# interface-2-cart.net
KiCad netlist of a schematic drawn in EAGLE
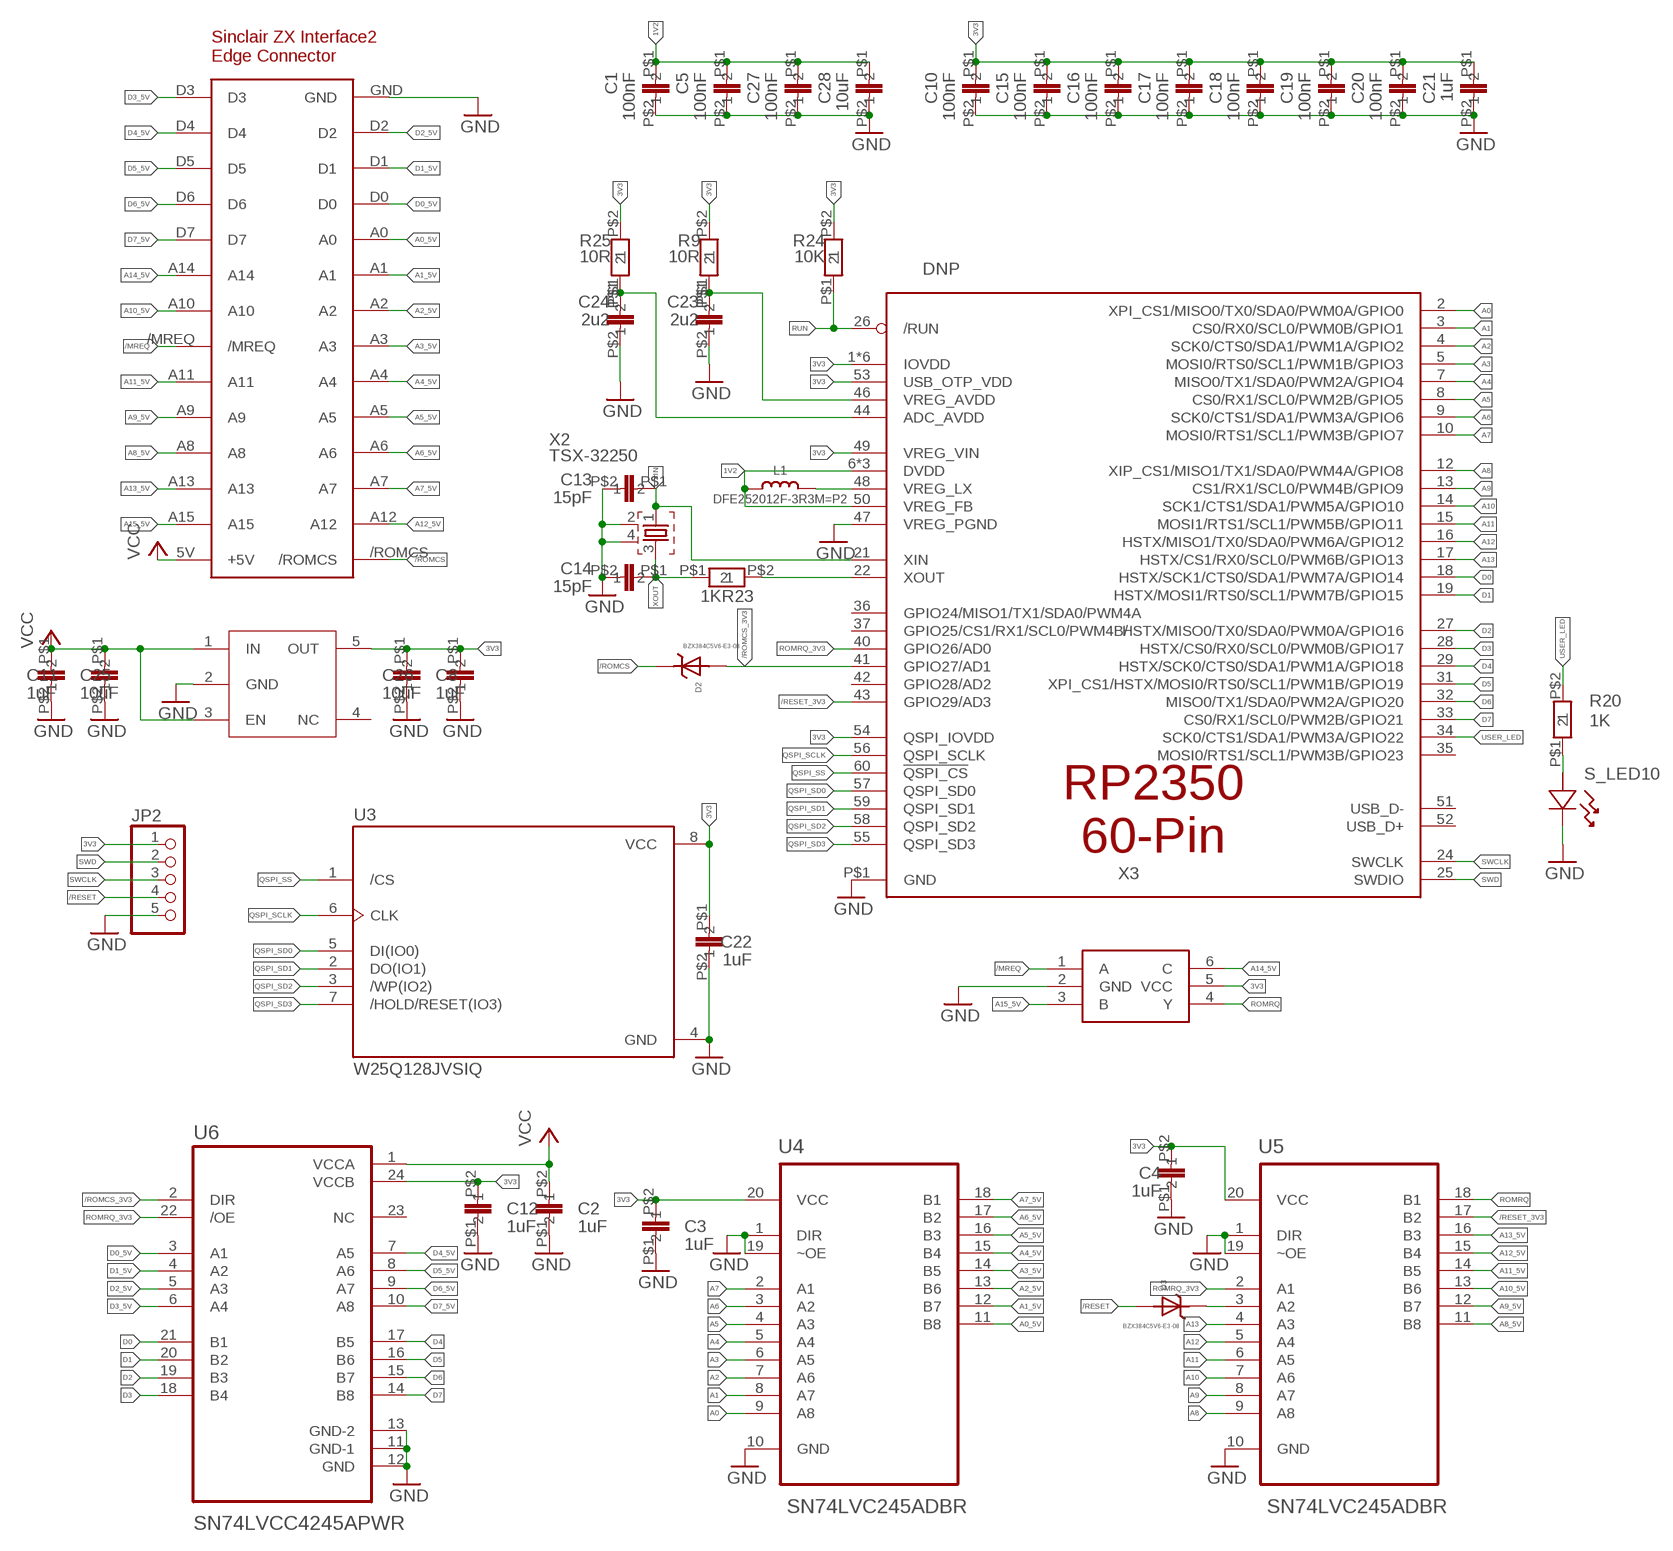
[diagram p0: schematic, sheet 1]

(export (version "E")
  (design (tool "Eeschema 10.0.6"))
  (components
    (comp (ref "3V3_REG2")
      (value "3V3")
      (footprint "eagle-import:NCP718BSN330T1G")
      (libsource (lib "eagle-import") (part "NCP718BSN330T1G"))
    )
    (comp (ref "C1")
      (value "100nF")
      (footprint "eagle-import:C0402")
      (libsource (lib "eagle-import") (part "CAP-0402"))
    )
    (comp (ref "C2")
      (value "1uF")
      (footprint "eagle-import:C0402")
      (libsource (lib "eagle-import") (part "CAP-0402"))
    )
    (comp (ref "C3")
      (value "1uF")
      (footprint "eagle-import:C0402")
      (libsource (lib "eagle-import") (part "CAP-0402"))
    )
    (comp (ref "C4")
      (value "1uF")
      (footprint "eagle-import:C0402")
      (libsource (lib "eagle-import") (part "CAP-0402"))
    )
    (comp (ref "C5")
      (value "100nF")
      (footprint "eagle-import:C0402")
      (libsource (lib "eagle-import") (part "CAP-0402"))
    )
    (comp (ref "C8")
      (value "1uF")
      (footprint "eagle-import:C0402")
      (libsource (lib "eagle-import") (part "CAP-0402"))
    )
    (comp (ref "C10")
      (value "100nF")
      (footprint "eagle-import:C0402")
      (libsource (lib "eagle-import") (part "CAP-0402"))
    )
    (comp (ref "C11")
      (value "1uF")
      (footprint "eagle-import:C0402")
      (libsource (lib "eagle-import") (part "CAP-0402"))
    )
    (comp (ref "C12")
      (value "1uF")
      (footprint "eagle-import:C0402")
      (libsource (lib "eagle-import") (part "CAP-0402"))
    )
    (comp (ref "C13")
      (value "15pF")
      (footprint "eagle-import:C0402")
      (libsource (lib "eagle-import") (part "CAP-0402"))
    )
    (comp (ref "C14")
      (value "15pF")
      (footprint "eagle-import:C0402")
      (libsource (lib "eagle-import") (part "CAP-0402"))
    )
    (comp (ref "C15")
      (value "100nF")
      (footprint "eagle-import:C0402")
      (libsource (lib "eagle-import") (part "CAP-0402"))
    )
    (comp (ref "C16")
      (value "100nF")
      (footprint "eagle-import:C0402")
      (libsource (lib "eagle-import") (part "CAP-0402"))
    )
    (comp (ref "C17")
      (value "100nF")
      (footprint "eagle-import:C0402")
      (libsource (lib "eagle-import") (part "CAP-0402"))
    )
    (comp (ref "C18")
      (value "100nF")
      (footprint "eagle-import:C0402")
      (libsource (lib "eagle-import") (part "CAP-0402"))
    )
    (comp (ref "C19")
      (value "100nF")
      (footprint "eagle-import:C0402")
      (libsource (lib "eagle-import") (part "CAP-0402"))
    )
    (comp (ref "C20")
      (value "100nF")
      (footprint "eagle-import:C0402")
      (libsource (lib "eagle-import") (part "CAP-0402"))
    )
    (comp (ref "C21")
      (value "1uF")
      (footprint "eagle-import:C0402")
      (libsource (lib "eagle-import") (part "CAP-0402"))
    )
    (comp (ref "C22")
      (value "1uF")
      (footprint "eagle-import:C0402")
      (libsource (lib "eagle-import") (part "CAP-0402"))
    )
    (comp (ref "C23")
      (value "2u2")
      (footprint "eagle-import:C0402")
      (libsource (lib "eagle-import") (part "CAP-0402"))
    )
    (comp (ref "C24")
      (value "2u2")
      (footprint "eagle-import:C0402")
      (libsource (lib "eagle-import") (part "CAP-0402"))
    )
    (comp (ref "C25")
      (value "10uF")
      (footprint "eagle-import:C0402")
      (libsource (lib "eagle-import") (part "CAP-0402"))
    )
    (comp (ref "C26")
      (value "10uF")
      (footprint "eagle-import:C0402")
      (libsource (lib "eagle-import") (part "CAP-0402"))
    )
    (comp (ref "C27")
      (value "100nF")
      (footprint "eagle-import:C0402")
      (libsource (lib "eagle-import") (part "CAP-0402"))
    )
    (comp (ref "C28")
      (value "10uF")
      (footprint "eagle-import:C0402")
      (libsource (lib "eagle-import") (part "CAP-0402"))
    )
    (comp (ref "D2")
      (value "BZX384C5V6-E3-08")
      (footprint "eagle-import:SOD-323")
      (fields (field (name "MF") "Vishay Semiconductors"))
      (libsource (lib "eagle-import") (part "BZX384C5V6-E3-08"))
    )
    (comp (ref "D3")
      (value "BZX384C5V6-E3-08")
      (footprint "eagle-import:SOD-323")
      (fields (field (name "MF") "Vishay Semiconductors"))
      (libsource (lib "eagle-import") (part "BZX384C5V6-E3-08"))
    )
    (comp (ref "JP2")
      (value "PINHD-1X5")
      (footprint "eagle-import:1X05")
      (libsource (lib "eagle-import") (part "PINHD-1X5"))
    )
    (comp (ref "L1")
      (value "DFE252012F-3R3M=P2")
      (footprint "eagle-import:INDUCTOR_1007")
      (libsource (lib "eagle-import") (part "INDUCTOR"))
    )
    (comp (ref "R9")
      (value "10R")
      (footprint "eagle-import:0402")
      (libsource (lib "eagle-import") (part "RES-0402"))
    )
    (comp (ref "R20")
      (value "1K")
      (footprint "eagle-import:0402")
      (libsource (lib "eagle-import") (part "RES-0402"))
    )
    (comp (ref "R23")
      (value "1K")
      (footprint "eagle-import:0402")
      (libsource (lib "eagle-import") (part "RES-0402"))
    )
    (comp (ref "R24")
      (value "10K")
      (footprint "eagle-import:0402")
      (libsource (lib "eagle-import") (part "RES-0402"))
    )
    (comp (ref "R25")
      (value "10R")
      (footprint "eagle-import:0402")
      (libsource (lib "eagle-import") (part "RES-0402"))
    )
    (comp (ref "S_LED10")
      (value "20mA")
      (footprint "eagle-import:LED_VLMW15_VIS")
      (fields
        (field (name "MANUFACTURER_PART_NUMBER") "VLMW1500-GS08")
        (field (name "COPYRIGHT") "Copyright (C) 2022 Ultra Librarian. All rights reserved.")
      )
      (libsource (lib "eagle-import") (part "VLMW1500-GS08"))
    )
    (comp (ref "U$1")
      (value "ZX_I2_ROM_EDGE_CONNECTOR")
      (footprint "eagle-import:ZX_I2_ROM_EDGE_CONNECTOR_V2")
      (libsource (lib "eagle-import") (part "ZX_I2_ROM_EDGE_CONNECTOR"))
    )
    (comp (ref "U$2")
      (value "74LVC1G332GW,125")
      (footprint "eagle-import:SOP65P210X110-6N")
      (libsource (lib "eagle-import") (part "74LVC1G332GW,125"))
    )
    (comp (ref "U3")
      (value "W25Q128JVSIQ")
      (footprint "eagle-import:SOIC127P790X216-8N")
      (fields (field (name "MF") "Winbond Electronics"))
      (libsource (lib "eagle-import") (part "W25Q128JVSIQ"))
    )
    (comp (ref "U4")
      (value "SN74LVC245ADBR")
      (footprint "eagle-import:SOP65P780X200-20N")
      (fields (field (name "MF") "Texas Instruments"))
      (libsource (lib "eagle-import") (part "SN74LVC245ADBR"))
    )
    (comp (ref "U5")
      (value "SN74LVC245ADBR")
      (footprint "eagle-import:SOP65P780X200-20N")
      (fields (field (name "MF") "Texas Instruments"))
      (libsource (lib "eagle-import") (part "SN74LVC245ADBR"))
    )
    (comp (ref "U6")
      (value "SN74LVCC4245APWR")
      (footprint "eagle-import:SOP65P640X120-24N")
      (fields (field (name "MF") "Texas Instruments"))
      (libsource (lib "eagle-import") (part "SN74LVCC4245APWR"))
    )
    (comp (ref "X2")
      (value "TSX-32250")
      (footprint "eagle-import:TSX-3225")
      (fields (field (name "MF") "EPSON") (field (name "MP") "TSX-3225"))
      (libsource (lib "eagle-import") (part "TSX-32250"))
    )
    (comp (ref "X3")
      (value "DNP")
      (footprint "eagle-import:QFN60_7MM_REDUCEDEPAD")
      (libsource (lib "eagle-import") (part "RP2350_QFN60"))
    )
  )
  (nets
    (net (code "1") (name "1V2") (class "Default")
      (node (ref "C1") (pin "P$1") (pinfunction "1_P$1") (pintype "passive"))
      (node (ref "C27") (pin "P$1") (pinfunction "1_P$1") (pintype "passive"))
      (node (ref "C28") (pin "P$1") (pinfunction "1_P$1") (pintype "passive"))
      (node (ref "C5") (pin "P$1") (pinfunction "1_P$1") (pintype "passive"))
      (node (ref "L1") (pin "P$1") (pinfunction "1_P$1") (pintype "passive"))
      (node (ref "X3") (pin "23") (pinfunction "DVDD_23") (pintype "power_in"))
      (node (ref "X3") (pin "39") (pinfunction "DVDD_39") (pintype "power_in"))
      (node (ref "X3") (pin "50") (pinfunction "VREG_FB_50") (pintype "input"))
      (node (ref "X3") (pin "6") (pinfunction "DVDD_6") (pintype "power_in"))
    )
    (net (code "2") (name "3V3") (class "Default")
      (node (ref "3V3_REG2") (pin "5") (pinfunction "OUT_5") (pintype "power_in"))
      (node (ref "C10") (pin "P$1") (pinfunction "1_P$1") (pintype "passive"))
      (node (ref "C12") (pin "P$2") (pinfunction "2_P$2") (pintype "passive"))
      (node (ref "C15") (pin "P$1") (pinfunction "1_P$1") (pintype "passive"))
      (node (ref "C16") (pin "P$1") (pinfunction "1_P$1") (pintype "passive"))
      (node (ref "C17") (pin "P$1") (pinfunction "1_P$1") (pintype "passive"))
      (node (ref "C18") (pin "P$1") (pinfunction "1_P$1") (pintype "passive"))
      (node (ref "C19") (pin "P$1") (pinfunction "1_P$1") (pintype "passive"))
      (node (ref "C20") (pin "P$1") (pinfunction "1_P$1") (pintype "passive"))
      (node (ref "C21") (pin "P$1") (pinfunction "1_P$1") (pintype "passive"))
      (node (ref "C22") (pin "P$1") (pinfunction "1_P$1") (pintype "passive"))
      (node (ref "C26") (pin "P$1") (pinfunction "1_P$1") (pintype "passive"))
      (node (ref "C3") (pin "P$2") (pinfunction "2_P$2") (pintype "passive"))
      (node (ref "C4") (pin "P$2") (pinfunction "2_P$2") (pintype "passive"))
      (node (ref "C8") (pin "P$1") (pinfunction "1_P$1") (pintype "passive"))
      (node (ref "JP2") (pin "1") (pinfunction "1_1") (pintype "passive"))
      (node (ref "R24") (pin "P$2") (pinfunction "2_P$2") (pintype "passive"))
      (node (ref "R25") (pin "P$2") (pinfunction "2_P$2") (pintype "passive"))
      (node (ref "R9") (pin "P$2") (pinfunction "2_P$2") (pintype "passive"))
      (node (ref "U$2") (pin "5") (pinfunction "VCC_5") (pintype "bidirectional"))
      (node (ref "U3") (pin "8") (pinfunction "VCC_8") (pintype "power_in"))
      (node (ref "U4") (pin "20") (pinfunction "VCC_20") (pintype "power_in"))
      (node (ref "U5") (pin "20") (pinfunction "VCC_20") (pintype "power_in"))
      (node (ref "U6") (pin "24") (pinfunction "VCCB_24") (pintype "power_in"))
      (node (ref "X3") (pin "1") (pinfunction "IOVDD_1") (pintype "power_in"))
      (node (ref "X3") (pin "11") (pinfunction "IOVDD_11") (pintype "power_in"))
      (node (ref "X3") (pin "20") (pinfunction "IOVDD_20") (pintype "power_in"))
      (node (ref "X3") (pin "30") (pinfunction "IOVDD_30") (pintype "power_in"))
      (node (ref "X3") (pin "38") (pinfunction "IOVDD_38") (pintype "power_in"))
      (node (ref "X3") (pin "45") (pinfunction "IOVDD_45") (pintype "power_in"))
      (node (ref "X3") (pin "49") (pinfunction "VREG_VIN_49") (pintype "input"))
      (node (ref "X3") (pin "53") (pinfunction "USB_OTP_VDD_53") (pintype "power_in"))
      (node (ref "X3") (pin "54") (pinfunction "QSPI_IOVDD_54") (pintype "power_in"))
    )
    (net (code "3") (name "A0") (class "Default")
      (node (ref "U4") (pin "9") (pinfunction "A8_9") (pintype "bidirectional"))
      (node (ref "X3") (pin "2") (pinfunction "XPI_CS1/MISO0/TX0/SDA0/PWM0A/GPIO0_2") (pintype "bidirectional"))
    )
    (net (code "4") (name "A0_5V") (class "Default")
      (node (ref "U$1") (pin "A0") (pinfunction "A0_A0") (pintype "bidirectional"))
      (node (ref "U4") (pin "11") (pinfunction "B8_11") (pintype "bidirectional"))
    )
    (net (code "5") (name "A1") (class "Default")
      (node (ref "U4") (pin "8") (pinfunction "A7_8") (pintype "bidirectional"))
      (node (ref "X3") (pin "3") (pinfunction "CS0/RX0/SCL0/PWM0B/GPIO1_3") (pintype "bidirectional"))
    )
    (net (code "6") (name "A1_5V") (class "Default")
      (node (ref "U$1") (pin "A1") (pinfunction "A1_A1") (pintype "bidirectional"))
      (node (ref "U4") (pin "12") (pinfunction "B7_12") (pintype "bidirectional"))
    )
    (net (code "7") (name "A2") (class "Default")
      (node (ref "U4") (pin "7") (pinfunction "A6_7") (pintype "bidirectional"))
      (node (ref "X3") (pin "4") (pinfunction "SCK0/CTS0/SDA1/PWM1A/GPIO2_4") (pintype "bidirectional"))
    )
    (net (code "8") (name "A2_5V") (class "Default")
      (node (ref "U$1") (pin "A2") (pinfunction "A2_A2") (pintype "bidirectional"))
      (node (ref "U4") (pin "13") (pinfunction "B6_13") (pintype "bidirectional"))
    )
    (net (code "9") (name "A3") (class "Default")
      (node (ref "U4") (pin "6") (pinfunction "A5_6") (pintype "bidirectional"))
      (node (ref "X3") (pin "5") (pinfunction "MOSI0/RTS0/SCL1/PWM1B/GPIO3_5") (pintype "bidirectional"))
    )
    (net (code "10") (name "A3_5V") (class "Default")
      (node (ref "U$1") (pin "A3") (pinfunction "A3_A3") (pintype "bidirectional"))
      (node (ref "U4") (pin "14") (pinfunction "B5_14") (pintype "bidirectional"))
    )
    (net (code "11") (name "A4") (class "Default")
      (node (ref "U4") (pin "5") (pinfunction "A4_5") (pintype "bidirectional"))
      (node (ref "X3") (pin "7") (pinfunction "MISO0/TX1/SDA0/PWM2A/GPIO4_7") (pintype "bidirectional"))
    )
    (net (code "12") (name "A4_5V") (class "Default")
      (node (ref "U$1") (pin "A4") (pinfunction "A4_A4") (pintype "bidirectional"))
      (node (ref "U4") (pin "15") (pinfunction "B4_15") (pintype "bidirectional"))
    )
    (net (code "13") (name "A5") (class "Default")
      (node (ref "U4") (pin "4") (pinfunction "A3_4") (pintype "bidirectional"))
      (node (ref "X3") (pin "8") (pinfunction "CS0/RX1/SCL0/PWM2B/GPIO5_8") (pintype "bidirectional"))
    )
    (net (code "14") (name "A5_5V") (class "Default")
      (node (ref "U$1") (pin "A5") (pinfunction "A5_A5") (pintype "bidirectional"))
      (node (ref "U4") (pin "16") (pinfunction "B3_16") (pintype "bidirectional"))
    )
    (net (code "15") (name "A6") (class "Default")
      (node (ref "U4") (pin "3") (pinfunction "A2_3") (pintype "bidirectional"))
      (node (ref "X3") (pin "9") (pinfunction "SCK0/CTS1/SDA1/PWM3A/GPIO6_9") (pintype "bidirectional"))
    )
    (net (code "16") (name "A6_5V") (class "Default")
      (node (ref "U$1") (pin "A6") (pinfunction "A6_A6") (pintype "bidirectional"))
      (node (ref "U4") (pin "17") (pinfunction "B2_17") (pintype "bidirectional"))
    )
    (net (code "17") (name "A7") (class "Default")
      (node (ref "U4") (pin "2") (pinfunction "A1_2") (pintype "bidirectional"))
      (node (ref "X3") (pin "10") (pinfunction "MOSI0/RTS1/SCL1/PWM3B/GPIO7_10") (pintype "bidirectional"))
    )
    (net (code "18") (name "A7_5V") (class "Default")
      (node (ref "U$1") (pin "A7") (pinfunction "A7_A7") (pintype "bidirectional"))
      (node (ref "U4") (pin "18") (pinfunction "B1_18") (pintype "bidirectional"))
    )
    (net (code "19") (name "A8") (class "Default")
      (node (ref "U5") (pin "9") (pinfunction "A8_9") (pintype "bidirectional"))
      (node (ref "X3") (pin "12") (pinfunction "XIP_CS1/MISO1/TX1/SDA0/PWM4A/GPIO8_12") (pintype "bidirectional"))
    )
    (net (code "20") (name "A8_5V") (class "Default")
      (node (ref "U$1") (pin "A8") (pinfunction "A8_A8") (pintype "bidirectional"))
      (node (ref "U5") (pin "11") (pinfunction "B8_11") (pintype "bidirectional"))
    )
    (net (code "21") (name "A9") (class "Default")
      (node (ref "U5") (pin "8") (pinfunction "A7_8") (pintype "bidirectional"))
      (node (ref "X3") (pin "13") (pinfunction "CS1/RX1/SCL0/PWM4B/GPIO9_13") (pintype "bidirectional"))
    )
    (net (code "22") (name "A9_5V") (class "Default")
      (node (ref "U$1") (pin "A9") (pinfunction "A9_A9") (pintype "bidirectional"))
      (node (ref "U5") (pin "12") (pinfunction "B7_12") (pintype "bidirectional"))
    )
    (net (code "23") (name "A10") (class "Default")
      (node (ref "U5") (pin "7") (pinfunction "A6_7") (pintype "bidirectional"))
      (node (ref "X3") (pin "14") (pinfunction "SCK1/CTS1/SDA1/PWM5A/GPIO10_14") (pintype "bidirectional"))
    )
    (net (code "24") (name "A10_5V") (class "Default")
      (node (ref "U$1") (pin "A10") (pinfunction "A10_A10") (pintype "bidirectional"))
      (node (ref "U5") (pin "13") (pinfunction "B6_13") (pintype "bidirectional"))
    )
    (net (code "25") (name "A11") (class "Default")
      (node (ref "U5") (pin "6") (pinfunction "A5_6") (pintype "bidirectional"))
      (node (ref "X3") (pin "15") (pinfunction "MOSI1/RTS1/SCL1/PWM5B/GPIO11_15") (pintype "bidirectional"))
    )
    (net (code "26") (name "A11_5V") (class "Default")
      (node (ref "U$1") (pin "A11") (pinfunction "A11_A11") (pintype "bidirectional"))
      (node (ref "U5") (pin "14") (pinfunction "B5_14") (pintype "bidirectional"))
    )
    (net (code "27") (name "A12") (class "Default")
      (node (ref "U5") (pin "5") (pinfunction "A4_5") (pintype "bidirectional"))
      (node (ref "X3") (pin "16") (pinfunction "HSTX/MISO1/TX0/SDA0/PWM6A/GPIO12_16") (pintype "bidirectional"))
    )
    (net (code "28") (name "A12_5V") (class "Default")
      (node (ref "U$1") (pin "A12") (pinfunction "A12_A12") (pintype "bidirectional"))
      (node (ref "U5") (pin "15") (pinfunction "B4_15") (pintype "bidirectional"))
    )
    (net (code "29") (name "A13") (class "Default")
      (node (ref "U5") (pin "4") (pinfunction "A3_4") (pintype "bidirectional"))
      (node (ref "X3") (pin "17") (pinfunction "HSTX/CS1/RX0/SCL0/PWM6B/GPIO13_17") (pintype "bidirectional"))
    )
    (net (code "30") (name "A13_5V") (class "Default")
      (node (ref "U$1") (pin "A13") (pinfunction "A13_A13") (pintype "bidirectional"))
      (node (ref "U5") (pin "16") (pinfunction "B3_16") (pintype "bidirectional"))
    )
    (net (code "31") (name "A14_5V") (class "Default")
      (node (ref "U$1") (pin "A14") (pinfunction "A14_A14") (pintype "bidirectional"))
      (node (ref "U$2") (pin "6") (pinfunction "C_6") (pintype "bidirectional"))
    )
    (net (code "32") (name "A15_5V") (class "Default")
      (node (ref "U$1") (pin "A15") (pinfunction "A15_A15") (pintype "bidirectional"))
      (node (ref "U$2") (pin "3") (pinfunction "B_3") (pintype "bidirectional"))
    )
    (net (code "33") (name "D0") (class "Default")
      (node (ref "U6") (pin "21") (pinfunction "B1_21") (pintype "bidirectional"))
      (node (ref "X3") (pin "18") (pinfunction "HSTX/SCK1/CTS0/SDA1/PWM7A/GPIO14_18") (pintype "bidirectional"))
    )
    (net (code "34") (name "D0_5V") (class "Default")
      (node (ref "U$1") (pin "D0") (pinfunction "D0_D0") (pintype "bidirectional"))
      (node (ref "U6") (pin "3") (pinfunction "A1_3") (pintype "bidirectional"))
    )
    (net (code "35") (name "D1") (class "Default")
      (node (ref "U6") (pin "20") (pinfunction "B2_20") (pintype "bidirectional"))
      (node (ref "X3") (pin "19") (pinfunction "HSTX/MOSI1/RTS0/SCL1/PWM7B/GPIO15_19") (pintype "bidirectional"))
    )
    (net (code "36") (name "D1_5V") (class "Default")
      (node (ref "U$1") (pin "D1") (pinfunction "D1_D1") (pintype "bidirectional"))
      (node (ref "U6") (pin "4") (pinfunction "A2_4") (pintype "bidirectional"))
    )
    (net (code "37") (name "D2") (class "Default")
      (node (ref "U6") (pin "19") (pinfunction "B3_19") (pintype "bidirectional"))
      (node (ref "X3") (pin "27") (pinfunction "HSTX/MISO0/TX0/SDA0/PWM0A/GPIO16_27") (pintype "bidirectional"))
    )
    (net (code "38") (name "D2_5V") (class "Default")
      (node (ref "U$1") (pin "D2") (pinfunction "D2_D2") (pintype "bidirectional"))
      (node (ref "U6") (pin "5") (pinfunction "A3_5") (pintype "bidirectional"))
    )
    (net (code "39") (name "D3") (class "Default")
      (node (ref "U6") (pin "18") (pinfunction "B4_18") (pintype "bidirectional"))
      (node (ref "X3") (pin "28") (pinfunction "HSTX/CS0/RX0/SCL0/PWM0B/GPIO17_28") (pintype "bidirectional"))
    )
    (net (code "40") (name "D3_5V") (class "Default")
      (node (ref "U$1") (pin "D3") (pinfunction "D3_D3") (pintype "bidirectional"))
      (node (ref "U6") (pin "6") (pinfunction "A4_6") (pintype "bidirectional"))
    )
    (net (code "41") (name "D4") (class "Default")
      (node (ref "U6") (pin "17") (pinfunction "B5_17") (pintype "bidirectional"))
      (node (ref "X3") (pin "29") (pinfunction "HSTX/SCK0/CTS0/SDA1/PWM1A/GPIO18_29") (pintype "bidirectional"))
    )
    (net (code "42") (name "D4_5V") (class "Default")
      (node (ref "U$1") (pin "D4") (pinfunction "D4_D4") (pintype "bidirectional"))
      (node (ref "U6") (pin "7") (pinfunction "A5_7") (pintype "bidirectional"))
    )
    (net (code "43") (name "D5") (class "Default")
      (node (ref "U6") (pin "16") (pinfunction "B6_16") (pintype "bidirectional"))
      (node (ref "X3") (pin "31") (pinfunction "XPI_CS1/HSTX/MOSI0/RTS0/SCL1/PWM1B/GPIO19_31") (pintype "bidirectional"))
    )
    (net (code "44") (name "D5_5V") (class "Default")
      (node (ref "U$1") (pin "D5") (pinfunction "D5_D5") (pintype "bidirectional"))
      (node (ref "U6") (pin "8") (pinfunction "A6_8") (pintype "bidirectional"))
    )
    (net (code "45") (name "D6") (class "Default")
      (node (ref "U6") (pin "15") (pinfunction "B7_15") (pintype "bidirectional"))
      (node (ref "X3") (pin "32") (pinfunction "MISO0/TX1/SDA0/PWM2A/GPIO20_32") (pintype "bidirectional"))
    )
    (net (code "46") (name "D6_5V") (class "Default")
      (node (ref "U$1") (pin "D6") (pinfunction "D6_D6") (pintype "bidirectional"))
      (node (ref "U6") (pin "9") (pinfunction "A7_9") (pintype "bidirectional"))
    )
    (net (code "47") (name "D7") (class "Default")
      (node (ref "U6") (pin "14") (pinfunction "B8_14") (pintype "bidirectional"))
      (node (ref "X3") (pin "33") (pinfunction "CS0/RX1/SCL0/PWM2B/GPIO21_33") (pintype "bidirectional"))
    )
    (net (code "48") (name "D7_5V") (class "Default")
      (node (ref "U$1") (pin "D7") (pinfunction "D7_D7") (pintype "bidirectional"))
      (node (ref "U6") (pin "10") (pinfunction "A8_10") (pintype "bidirectional"))
    )
    (net (code "49") (name "GND") (class "Default")
      (node (ref "3V3_REG2") (pin "2") (pinfunction "GND_2") (pintype "power_in"))
      (node (ref "C1") (pin "P$2") (pinfunction "2_P$2") (pintype "passive"))
      (node (ref "C10") (pin "P$2") (pinfunction "2_P$2") (pintype "passive"))
      (node (ref "C11") (pin "P$2") (pinfunction "2_P$2") (pintype "passive"))
      (node (ref "C12") (pin "P$1") (pinfunction "1_P$1") (pintype "passive"))
      (node (ref "C13") (pin "P$2") (pinfunction "2_P$2") (pintype "passive"))
      (node (ref "C14") (pin "P$2") (pinfunction "2_P$2") (pintype "passive"))
      (node (ref "C15") (pin "P$2") (pinfunction "2_P$2") (pintype "passive"))
      (node (ref "C16") (pin "P$2") (pinfunction "2_P$2") (pintype "passive"))
      (node (ref "C17") (pin "P$2") (pinfunction "2_P$2") (pintype "passive"))
      (node (ref "C18") (pin "P$2") (pinfunction "2_P$2") (pintype "passive"))
      (node (ref "C19") (pin "P$2") (pinfunction "2_P$2") (pintype "passive"))
      (node (ref "C2") (pin "P$1") (pinfunction "1_P$1") (pintype "passive"))
      (node (ref "C20") (pin "P$2") (pinfunction "2_P$2") (pintype "passive"))
      (node (ref "C21") (pin "P$2") (pinfunction "2_P$2") (pintype "passive"))
      (node (ref "C22") (pin "P$2") (pinfunction "2_P$2") (pintype "passive"))
      (node (ref "C23") (pin "P$2") (pinfunction "2_P$2") (pintype "passive"))
      (node (ref "C24") (pin "P$2") (pinfunction "2_P$2") (pintype "passive"))
      (node (ref "C25") (pin "P$2") (pinfunction "2_P$2") (pintype "passive"))
      (node (ref "C26") (pin "P$2") (pinfunction "2_P$2") (pintype "passive"))
      (node (ref "C27") (pin "P$2") (pinfunction "2_P$2") (pintype "passive"))
      (node (ref "C28") (pin "P$2") (pinfunction "2_P$2") (pintype "passive"))
      (node (ref "C3") (pin "P$1") (pinfunction "1_P$1") (pintype "passive"))
      (node (ref "C4") (pin "P$1") (pinfunction "1_P$1") (pintype "passive"))
      (node (ref "C5") (pin "P$2") (pinfunction "2_P$2") (pintype "passive"))
      (node (ref "C8") (pin "P$2") (pinfunction "2_P$2") (pintype "passive"))
      (node (ref "JP2") (pin "5") (pinfunction "5_5") (pintype "passive"))
      (node (ref "S_LED10") (pin "C") (pinfunction "C_C") (pintype "passive"))
      (node (ref "U$1") (pin "GND") (pinfunction "GND_GND") (pintype "bidirectional"))
      (node (ref "U$2") (pin "2") (pinfunction "GND_2") (pintype "bidirectional"))
      (node (ref "U3") (pin "4") (pinfunction "GND_4") (pintype "power_in"))
      (node (ref "U4") (pin "1") (pinfunction "DIR_1") (pintype "input"))
      (node (ref "U4") (pin "10") (pinfunction "GND_10") (pintype "passive"))
      (node (ref "U4") (pin "19") (pinfunction "~{OE}_19") (pintype "bidirectional"))
      (node (ref "U5") (pin "1") (pinfunction "DIR_1") (pintype "input"))
      (node (ref "U5") (pin "10") (pinfunction "GND_10") (pintype "passive"))
      (node (ref "U5") (pin "19") (pinfunction "~{OE}_19") (pintype "bidirectional"))
      (node (ref "U6") (pin "11") (pinfunction "GND-1_11") (pintype "power_in"))
      (node (ref "U6") (pin "12") (pinfunction "GND_12") (pintype "power_in"))
      (node (ref "U6") (pin "13") (pinfunction "GND-2_13") (pintype "power_in"))
      (node (ref "X2") (pin "2") (pinfunction "2_2") (pintype "passive"))
      (node (ref "X2") (pin "4") (pinfunction "4_4") (pintype "passive"))
      (node (ref "X3") (pin "47") (pinfunction "VREG_PGND_47") (pintype "power_in"))
      (node (ref "X3") (pin "P$1") (pinfunction "GND_P$1") (pintype "power_in"))
    )
    (net (code "50") (name "Net-(C23-1)") (class "Default")
      (node (ref "C23") (pin "P$1") (pinfunction "1_P$1") (pintype "passive"))
      (node (ref "R9") (pin "P$1") (pinfunction "1_P$1") (pintype "passive"))
      (node (ref "X3") (pin "46") (pinfunction "VREG_AVDD_46") (pintype "power_in"))
    )
    (net (code "51") (name "Net-(C24-1)") (class "Default")
      (node (ref "C24") (pin "P$1") (pinfunction "1_P$1") (pintype "passive"))
      (node (ref "R25") (pin "P$1") (pinfunction "1_P$1") (pintype "passive"))
      (node (ref "X3") (pin "44") (pinfunction "ADC_AVDD_44") (pintype "power_in"))
    )
    (net (code "52") (name "Net-(L1-2)") (class "Default")
      (node (ref "L1") (pin "P$2") (pinfunction "2_P$2") (pintype "passive"))
      (node (ref "X3") (pin "48") (pinfunction "VREG_LX_48") (pintype "input"))
    )
    (net (code "53") (name "Net-(R20-1)") (class "Default")
      (node (ref "R20") (pin "P$1") (pinfunction "1_P$1") (pintype "passive"))
      (node (ref "S_LED10") (pin "A") (pinfunction "A_A") (pintype "passive"))
    )
    (net (code "54") (name "Net-(R23-2)") (class "Default")
      (node (ref "R23") (pin "P$2") (pinfunction "2_P$2") (pintype "passive"))
      (node (ref "X3") (pin "22") (pinfunction "XOUT_22") (pintype "output"))
    )
    (net (code "55") (name "Net-(U5-A2)") (class "Default")
      (node (ref "D3") (pin "C") (pinfunction "C_C") (pintype "passive"))
      (node (ref "U5") (pin "3") (pinfunction "A2_3") (pintype "bidirectional"))
    )
    (net (code "56") (name "QSPI_SCLK") (class "Default")
      (node (ref "U3") (pin "6") (pinfunction "CLK_6") (pintype "input"))
      (node (ref "X3") (pin "56") (pinfunction "QSPI_SCLK_56") (pintype "bidirectional"))
    )
    (net (code "57") (name "QSPI_SD0") (class "Default")
      (node (ref "U3") (pin "5") (pinfunction "DI(IO0)_5") (pintype "bidirectional"))
      (node (ref "X3") (pin "57") (pinfunction "QSPI_SD0_57") (pintype "bidirectional"))
    )
    (net (code "58") (name "QSPI_SD1") (class "Default")
      (node (ref "U3") (pin "2") (pinfunction "DO(IO1)_2") (pintype "bidirectional"))
      (node (ref "X3") (pin "59") (pinfunction "QSPI_SD1_59") (pintype "bidirectional"))
    )
    (net (code "59") (name "QSPI_SD2") (class "Default")
      (node (ref "U3") (pin "3") (pinfunction "/WP(IO2)_3") (pintype "bidirectional"))
      (node (ref "X3") (pin "58") (pinfunction "QSPI_SD2_58") (pintype "bidirectional"))
    )
    (net (code "60") (name "QSPI_SD3") (class "Default")
      (node (ref "U3") (pin "7") (pinfunction "/HOLD/RESET(IO3)_7") (pintype "bidirectional"))
      (node (ref "X3") (pin "55") (pinfunction "QSPI_SD3_55") (pintype "bidirectional"))
    )
    (net (code "61") (name "QSPI_SS") (class "Default")
      (node (ref "U3") (pin "1") (pinfunction "/CS_1") (pintype "input"))
      (node (ref "X3") (pin "60") (pinfunction "~{QSPI_CS}_60") (pintype "bidirectional"))
    )
    (net (code "62") (name "ROMRQ") (class "Default")
      (node (ref "U$2") (pin "4") (pinfunction "Y_4") (pintype "bidirectional"))
      (node (ref "U5") (pin "18") (pinfunction "B1_18") (pintype "bidirectional"))
    )
    (net (code "63") (name "ROMRQ_3V3") (class "Default")
      (node (ref "U5") (pin "2") (pinfunction "A1_2") (pintype "bidirectional"))
      (node (ref "U6") (pin "22") (pinfunction "/OE_22") (pintype "bidirectional"))
      (node (ref "X3") (pin "40") (pinfunction "GPIO26/AD0_40") (pintype "bidirectional"))
    )
    (net (code "64") (name "RUN") (class "Default")
      (node (ref "R24") (pin "P$1") (pinfunction "1_P$1") (pintype "passive"))
      (node (ref "X3") (pin "26") (pinfunction "/RUN_26") (pintype "bidirectional"))
    )
    (net (code "65") (name "SWCLK") (class "Default")
      (node (ref "JP2") (pin "3") (pinfunction "3_3") (pintype "passive"))
      (node (ref "X3") (pin "24") (pinfunction "SWCLK_24") (pintype "bidirectional"))
    )
    (net (code "66") (name "SWD") (class "Default")
      (node (ref "JP2") (pin "2") (pinfunction "2_2") (pintype "passive"))
      (node (ref "X3") (pin "25") (pinfunction "SWDIO_25") (pintype "bidirectional"))
    )
    (net (code "67") (name "USER_LED") (class "Default")
      (node (ref "R20") (pin "P$2") (pinfunction "2_P$2") (pintype "passive"))
      (node (ref "X3") (pin "34") (pinfunction "SCK0/CTS1/SDA1/PWM3A/GPIO22_34") (pintype "bidirectional"))
    )
    (net (code "68") (name "VCC") (class "Default")
      (node (ref "3V3_REG2") (pin "1") (pinfunction "IN_1") (pintype "power_in"))
      (node (ref "3V3_REG2") (pin "3") (pinfunction "EN_3") (pintype "input"))
      (node (ref "C11") (pin "P$1") (pinfunction "1_P$1") (pintype "passive"))
      (node (ref "C2") (pin "P$2") (pinfunction "2_P$2") (pintype "passive"))
      (node (ref "C25") (pin "P$1") (pinfunction "1_P$1") (pintype "passive"))
      (node (ref "U$1") (pin "5V") (pinfunction "+5V_5V") (pintype "bidirectional"))
      (node (ref "U6") (pin "1") (pinfunction "VCCA_1") (pintype "power_in"))
    )
    (net (code "69") (name "XIN") (class "Default")
      (node (ref "C13") (pin "P$1") (pinfunction "1_P$1") (pintype "passive"))
      (node (ref "X2") (pin "1") (pinfunction "1_1") (pintype "passive"))
      (node (ref "X3") (pin "21") (pinfunction "XIN_21") (pintype "input"))
    )
    (net (code "70") (name "XOUT") (class "Default")
      (node (ref "C14") (pin "P$1") (pinfunction "1_P$1") (pintype "passive"))
      (node (ref "R23") (pin "P$1") (pinfunction "1_P$1") (pintype "passive"))
      (node (ref "X2") (pin "3") (pinfunction "3_3") (pintype "passive"))
    )
    (net (code "71") (name "unconnected-(3V3_REG2-NC-Pad4)") (class "Default")
      (node (ref "3V3_REG2") (pin "4") (pinfunction "NC_4") (pintype "no_connect"))
    )
    (net (code "72") (name "unconnected-(U6-NC-Pad23)") (class "Default")
      (node (ref "U6") (pin "23") (pinfunction "NC_23") (pintype "no_connect"))
    )
    (net (code "73") (name "unconnected-(X3-GPIO24{slash}MISO1{slash}TX1{slash}SDA0{slash}PWM4A-Pad36)") (class "Default")
      (node (ref "X3") (pin "36") (pinfunction "GPIO24/MISO1/TX1/SDA0/PWM4A_36") (pintype "bidirectional"))
    )
    (net (code "74") (name "unconnected-(X3-GPIO25{slash}CS1{slash}RX1{slash}SCL0{slash}PWM4B{slash}-Pad37)") (class "Default")
      (node (ref "X3") (pin "37") (pinfunction "GPIO25/CS1/RX1/SCL0/PWM4B/_37") (pintype "bidirectional"))
    )
    (net (code "75") (name "unconnected-(X3-GPIO28{slash}AD2-Pad42)") (class "Default")
      (node (ref "X3") (pin "42") (pinfunction "GPIO28/AD2_42") (pintype "bidirectional"))
    )
    (net (code "76") (name "unconnected-(X3-MOSI0{slash}RTS1{slash}SCL1{slash}PWM3B{slash}GPIO23-Pad35)") (class "Default")
      (node (ref "X3") (pin "35") (pinfunction "MOSI0/RTS1/SCL1/PWM3B/GPIO23_35") (pintype "bidirectional"))
    )
    (net (code "77") (name "unconnected-(X3-USB_D+-Pad52)") (class "Default")
      (node (ref "X3") (pin "52") (pinfunction "USB_D+_52") (pintype "bidirectional"))
    )
    (net (code "78") (name "unconnected-(X3-USB_D--Pad51)") (class "Default")
      (node (ref "X3") (pin "51") (pinfunction "USB_D-_51") (pintype "bidirectional"))
    )
    (net (code "79") (name "{slash}MREQ") (class "Default")
      (node (ref "U$1") (pin "/MREQ") (pinfunction "/MREQ_/MREQ") (pintype "bidirectional"))
      (node (ref "U$2") (pin "1") (pinfunction "A_1") (pintype "bidirectional"))
    )
    (net (code "80") (name "{slash}RESET") (class "Default")
      (node (ref "D3") (pin "A") (pinfunction "A_A") (pintype "passive"))
      (node (ref "JP2") (pin "4") (pinfunction "4_4") (pintype "passive"))
    )
    (net (code "81") (name "{slash}RESET_3V3") (class "Default")
      (node (ref "U5") (pin "17") (pinfunction "B2_17") (pintype "bidirectional"))
      (node (ref "X3") (pin "43") (pinfunction "GPIO29/AD3_43") (pintype "bidirectional"))
    )
    (net (code "82") (name "{slash}ROMCS") (class "Default")
      (node (ref "D2") (pin "C") (pinfunction "C_C") (pintype "passive"))
      (node (ref "U$1") (pin "/ROMCS") (pinfunction "/ROMCS_/ROMCS") (pintype "bidirectional"))
    )
    (net (code "83") (name "{slash}ROMCS_3V3") (class "Default")
      (node (ref "D2") (pin "A") (pinfunction "A_A") (pintype "passive"))
      (node (ref "U6") (pin "2") (pinfunction "DIR_2") (pintype "input"))
      (node (ref "X3") (pin "41") (pinfunction "GPIO27/AD1_41") (pintype "bidirectional"))
    )
  )
)
